# E36.net
KiCad netlist of a schematic drawn in EAGLE
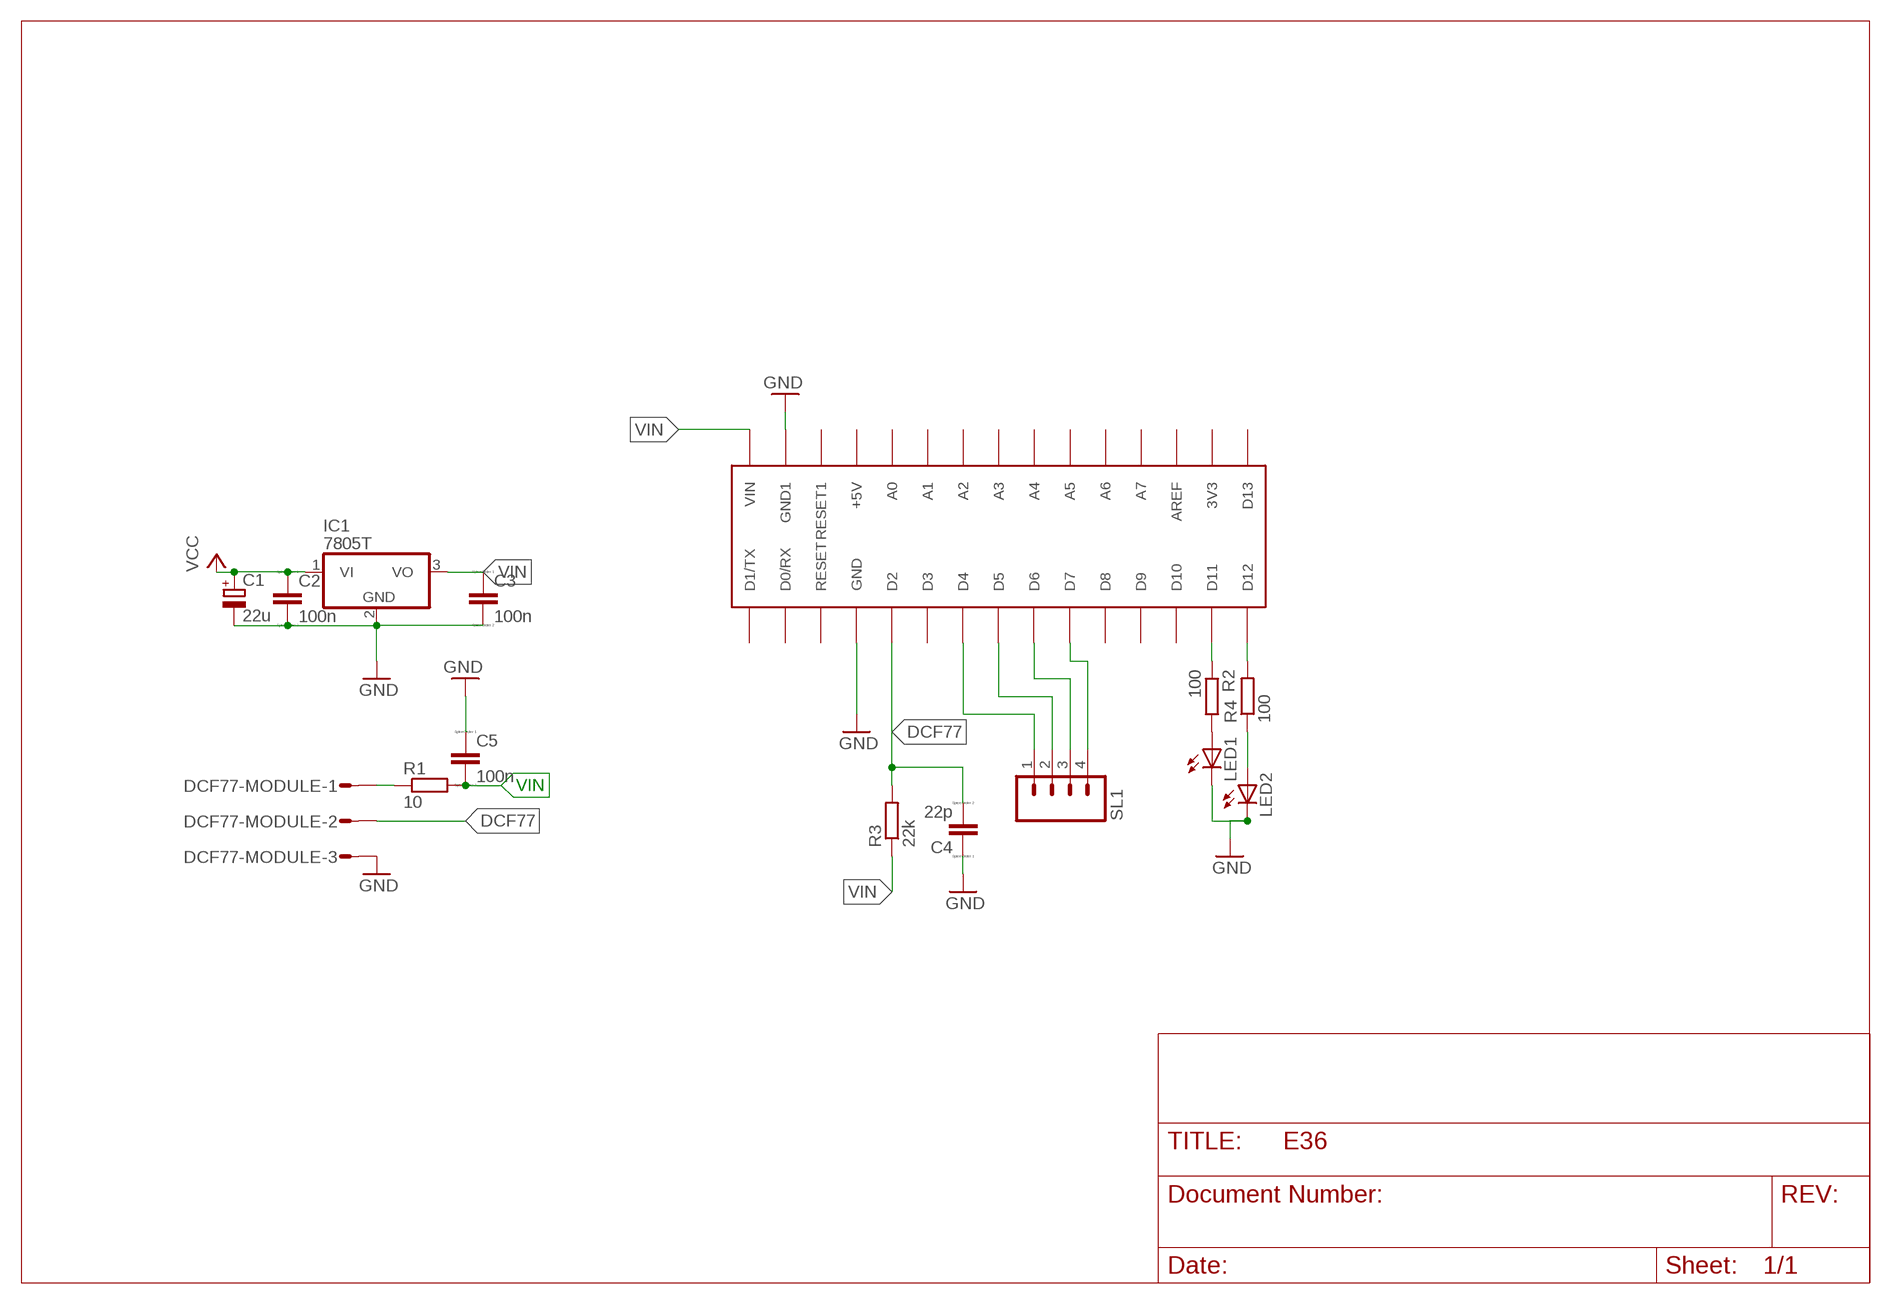
[diagram p0: schematic, sheet 1]

(export (version "E")
  (design (tool "Eeschema 10.0.6"))
  (components
    (comp (ref "C1")
      (value "22u")
      (footprint "eagle-import:E2,5-6E")
      (libsource (lib "eagle-import") (part "CPOL-EUE2,5-6E"))
    )
    (comp (ref "C2")
      (value "100n")
      (footprint "eagle-import:C025-025X050")
      (libsource (lib "eagle-import") (part "C-EU025-025X050"))
    )
    (comp (ref "C3")
      (value "100n")
      (footprint "eagle-import:C025-025X050")
      (libsource (lib "eagle-import") (part "C-EU025-025X050"))
    )
    (comp (ref "C4")
      (value "22p")
      (footprint "eagle-import:C025-025X050")
      (libsource (lib "eagle-import") (part "C-EU025-025X050"))
    )
    (comp (ref "C5")
      (value "100n")
      (footprint "eagle-import:C025-025X050")
      (libsource (lib "eagle-import") (part "C-EU025-025X050"))
    )
    (comp (ref "DCF77-MODULE")
      (value "MT6-3Y")
      (footprint "eagle-import:MT6-3Y")
      (libsource (lib "eagle-import") (part "MT6-3Y"))
    )
    (comp (ref "IC1")
      (value "7805T")
      (footprint "eagle-import:TO220H")
      (libsource (lib "eagle-import") (part "78T05"))
    )
    (comp (ref "LED1")
      (value "LED3MM")
      (footprint "eagle-import:LED3MM")
      (libsource (lib "eagle-import") (part "LED3MM"))
    )
    (comp (ref "LED2")
      (value "LED3MM")
      (footprint "eagle-import:LED3MM")
      (libsource (lib "eagle-import") (part "LED3MM"))
    )
    (comp (ref "R1")
      (value "10")
      (footprint "eagle-import:0204_7")
      (libsource (lib "eagle-import") (part "R-EU_0204/7"))
    )
    (comp (ref "R2")
      (value "100")
      (footprint "eagle-import:0204_7")
      (libsource (lib "eagle-import") (part "R-EU_0204/7"))
    )
    (comp (ref "R3")
      (value "22k")
      (footprint "eagle-import:0204_7")
      (libsource (lib "eagle-import") (part "R-EU_0204/7"))
    )
    (comp (ref "R4")
      (value "100")
      (footprint "eagle-import:0204_7")
      (libsource (lib "eagle-import") (part "R-EU_0204/7"))
    )
    (comp (ref "SL1")
      (value "M04")
      (footprint "eagle-import:04P")
      (libsource (lib "eagle-import") (part "M04"))
    )
    (comp (ref "U$1")
      (value "ARDUINONANO")
      (footprint "eagle-import:PDIP-32")
      (libsource (lib "eagle-import") (part "ARDUINONANO"))
    )
  )
  (nets
    (net (code "1") (name "DCF77") (class "Default")
      (node (ref "C4") (pin "2") (pinfunction "2_2") (pintype "passive"))
      (node (ref "DCF77-MODULE") (pin "2") (pinfunction "S_2") (pintype "passive"))
      (node (ref "R3") (pin "2") (pinfunction "2_2") (pintype "passive"))
      (node (ref "U$1") (pin "D2") (pinfunction "D2_D2") (pintype "bidirectional"))
    )
    (net (code "2") (name "GND") (class "Default")
      (node (ref "C1") (pin "-") (pinfunction "-_-") (pintype "passive"))
      (node (ref "C2") (pin "2") (pinfunction "2_2") (pintype "passive"))
      (node (ref "C3") (pin "2") (pinfunction "2_2") (pintype "passive"))
      (node (ref "C4") (pin "1") (pinfunction "1_1") (pintype "passive"))
      (node (ref "C5") (pin "1") (pinfunction "1_1") (pintype "passive"))
      (node (ref "DCF77-MODULE") (pin "3") (pinfunction "S_3") (pintype "passive"))
      (node (ref "IC1") (pin "2") (pinfunction "GND_2") (pintype "passive"))
      (node (ref "LED1") (pin "K") (pinfunction "C_K") (pintype "passive"))
      (node (ref "LED2") (pin "K") (pinfunction "C_K") (pintype "passive"))
      (node (ref "U$1") (pin "GND") (pinfunction "GND_GND") (pintype "bidirectional"))
      (node (ref "U$1") (pin "GND1") (pinfunction "GND1_GND1") (pintype "bidirectional"))
    )
    (net (code "3") (name "Net-(DCF77-MODULEA-S)") (class "Default")
      (node (ref "DCF77-MODULE") (pin "1") (pinfunction "S_1") (pintype "passive"))
      (node (ref "R1") (pin "1") (pinfunction "1_1") (pintype "passive"))
    )
    (net (code "4") (name "Net-(LED1-PadA)") (class "Default")
      (node (ref "LED1") (pin "A") (pinfunction "A_A") (pintype "passive"))
      (node (ref "R2") (pin "2") (pinfunction "2_2") (pintype "passive"))
    )
    (net (code "5") (name "Net-(LED2-PadA)") (class "Default")
      (node (ref "LED2") (pin "A") (pinfunction "A_A") (pintype "passive"))
      (node (ref "R4") (pin "1") (pinfunction "1_1") (pintype "passive"))
    )
    (net (code "6") (name "Net-(R2-Pad1)") (class "Default")
      (node (ref "R2") (pin "1") (pinfunction "1_1") (pintype "passive"))
      (node (ref "U$1") (pin "D11") (pinfunction "D11_D11") (pintype "bidirectional"))
    )
    (net (code "7") (name "Net-(R4-Pad2)") (class "Default")
      (node (ref "R4") (pin "2") (pinfunction "2_2") (pintype "passive"))
      (node (ref "U$1") (pin "D12") (pinfunction "D12_D12") (pintype "bidirectional"))
    )
    (net (code "8") (name "Net-(SL1-Pad1)") (class "Default")
      (node (ref "SL1") (pin "1") (pinfunction "1_1") (pintype "passive"))
      (node (ref "U$1") (pin "D4") (pinfunction "D4_D4") (pintype "bidirectional"))
    )
    (net (code "9") (name "Net-(SL1-Pad2)") (class "Default")
      (node (ref "SL1") (pin "2") (pinfunction "2_2") (pintype "passive"))
      (node (ref "U$1") (pin "D5") (pinfunction "D5_D5") (pintype "bidirectional"))
    )
    (net (code "10") (name "Net-(SL1-Pad3)") (class "Default")
      (node (ref "SL1") (pin "3") (pinfunction "3_3") (pintype "passive"))
      (node (ref "U$1") (pin "D6") (pinfunction "D6_D6") (pintype "bidirectional"))
    )
    (net (code "11") (name "Net-(SL1-Pad4)") (class "Default")
      (node (ref "SL1") (pin "4") (pinfunction "4_4") (pintype "passive"))
      (node (ref "U$1") (pin "D7") (pinfunction "D7_D7") (pintype "bidirectional"))
    )
    (net (code "12") (name "VCC") (class "Default")
      (node (ref "C1") (pin "+") (pinfunction "+_+") (pintype "passive"))
      (node (ref "C2") (pin "1") (pinfunction "1_1") (pintype "passive"))
      (node (ref "IC1") (pin "1") (pinfunction "VI_1") (pintype "input"))
    )
    (net (code "13") (name "VIN") (class "Default")
      (node (ref "C3") (pin "1") (pinfunction "1_1") (pintype "passive"))
      (node (ref "C5") (pin "2") (pinfunction "2_2") (pintype "passive"))
      (node (ref "IC1") (pin "3") (pinfunction "VO_3") (pintype "passive"))
      (node (ref "R1") (pin "2") (pinfunction "2_2") (pintype "passive"))
      (node (ref "R3") (pin "1") (pinfunction "1_1") (pintype "passive"))
      (node (ref "U$1") (pin "VIN") (pinfunction "VIN_VIN") (pintype "bidirectional"))
    )
    (net (code "14") (name "unconnected-(U$1-Pad+5V)") (class "Default")
      (node (ref "U$1") (pin "+5V") (pinfunction "+5V_+5V") (pintype "bidirectional"))
    )
    (net (code "15") (name "unconnected-(U$1-Pad3V3)") (class "Default")
      (node (ref "U$1") (pin "3V3") (pinfunction "3V3_3V3") (pintype "bidirectional"))
    )
    (net (code "16") (name "unconnected-(U$1-PadA0)") (class "Default")
      (node (ref "U$1") (pin "A0") (pinfunction "A0_A0") (pintype "bidirectional"))
    )
    (net (code "17") (name "unconnected-(U$1-PadA1)") (class "Default")
      (node (ref "U$1") (pin "A1") (pinfunction "A1_A1") (pintype "bidirectional"))
    )
    (net (code "18") (name "unconnected-(U$1-PadA2)") (class "Default")
      (node (ref "U$1") (pin "A2") (pinfunction "A2_A2") (pintype "bidirectional"))
    )
    (net (code "19") (name "unconnected-(U$1-PadA3)") (class "Default")
      (node (ref "U$1") (pin "A3") (pinfunction "A3_A3") (pintype "bidirectional"))
    )
    (net (code "20") (name "unconnected-(U$1-PadA4)") (class "Default")
      (node (ref "U$1") (pin "A4") (pinfunction "A4_A4") (pintype "bidirectional"))
    )
    (net (code "21") (name "unconnected-(U$1-PadA5)") (class "Default")
      (node (ref "U$1") (pin "A5") (pinfunction "A5_A5") (pintype "bidirectional"))
    )
    (net (code "22") (name "unconnected-(U$1-PadA6)") (class "Default")
      (node (ref "U$1") (pin "A6") (pinfunction "A6_A6") (pintype "bidirectional"))
    )
    (net (code "23") (name "unconnected-(U$1-PadA7)") (class "Default")
      (node (ref "U$1") (pin "A7") (pinfunction "A7_A7") (pintype "bidirectional"))
    )
    (net (code "24") (name "unconnected-(U$1-PadAREF)") (class "Default")
      (node (ref "U$1") (pin "AREF") (pinfunction "AREF_AREF") (pintype "bidirectional"))
    )
    (net (code "25") (name "unconnected-(U$1-PadD0{slash}RX)") (class "Default")
      (node (ref "U$1") (pin "D0/RX") (pinfunction "D0/RX_D0/RX") (pintype "bidirectional"))
    )
    (net (code "26") (name "unconnected-(U$1-PadD1{slash}TX)") (class "Default")
      (node (ref "U$1") (pin "D1/TX") (pinfunction "D1/TX_D1/TX") (pintype "bidirectional"))
    )
    (net (code "27") (name "unconnected-(U$1-PadD3)") (class "Default")
      (node (ref "U$1") (pin "D3") (pinfunction "D3_D3") (pintype "bidirectional"))
    )
    (net (code "28") (name "unconnected-(U$1-PadD8)") (class "Default")
      (node (ref "U$1") (pin "D8") (pinfunction "D8_D8") (pintype "bidirectional"))
    )
    (net (code "29") (name "unconnected-(U$1-PadD9)") (class "Default")
      (node (ref "U$1") (pin "D9") (pinfunction "D9_D9") (pintype "bidirectional"))
    )
    (net (code "30") (name "unconnected-(U$1-PadD10)") (class "Default")
      (node (ref "U$1") (pin "D10") (pinfunction "D10_D10") (pintype "bidirectional"))
    )
    (net (code "31") (name "unconnected-(U$1-PadD13)") (class "Default")
      (node (ref "U$1") (pin "D13") (pinfunction "D13_D13") (pintype "bidirectional"))
    )
    (net (code "32") (name "unconnected-(U$1-PadRESET)") (class "Default")
      (node (ref "U$1") (pin "RESET") (pinfunction "RESET_RESET") (pintype "bidirectional"))
    )
    (net (code "33") (name "unconnected-(U$1-PadRESET1)") (class "Default")
      (node (ref "U$1") (pin "RESET1") (pinfunction "RESET1_RESET1") (pintype "bidirectional"))
    )
  )
)
